# net_monitor.net
KiCad netlist of a schematic drawn in EAGLE
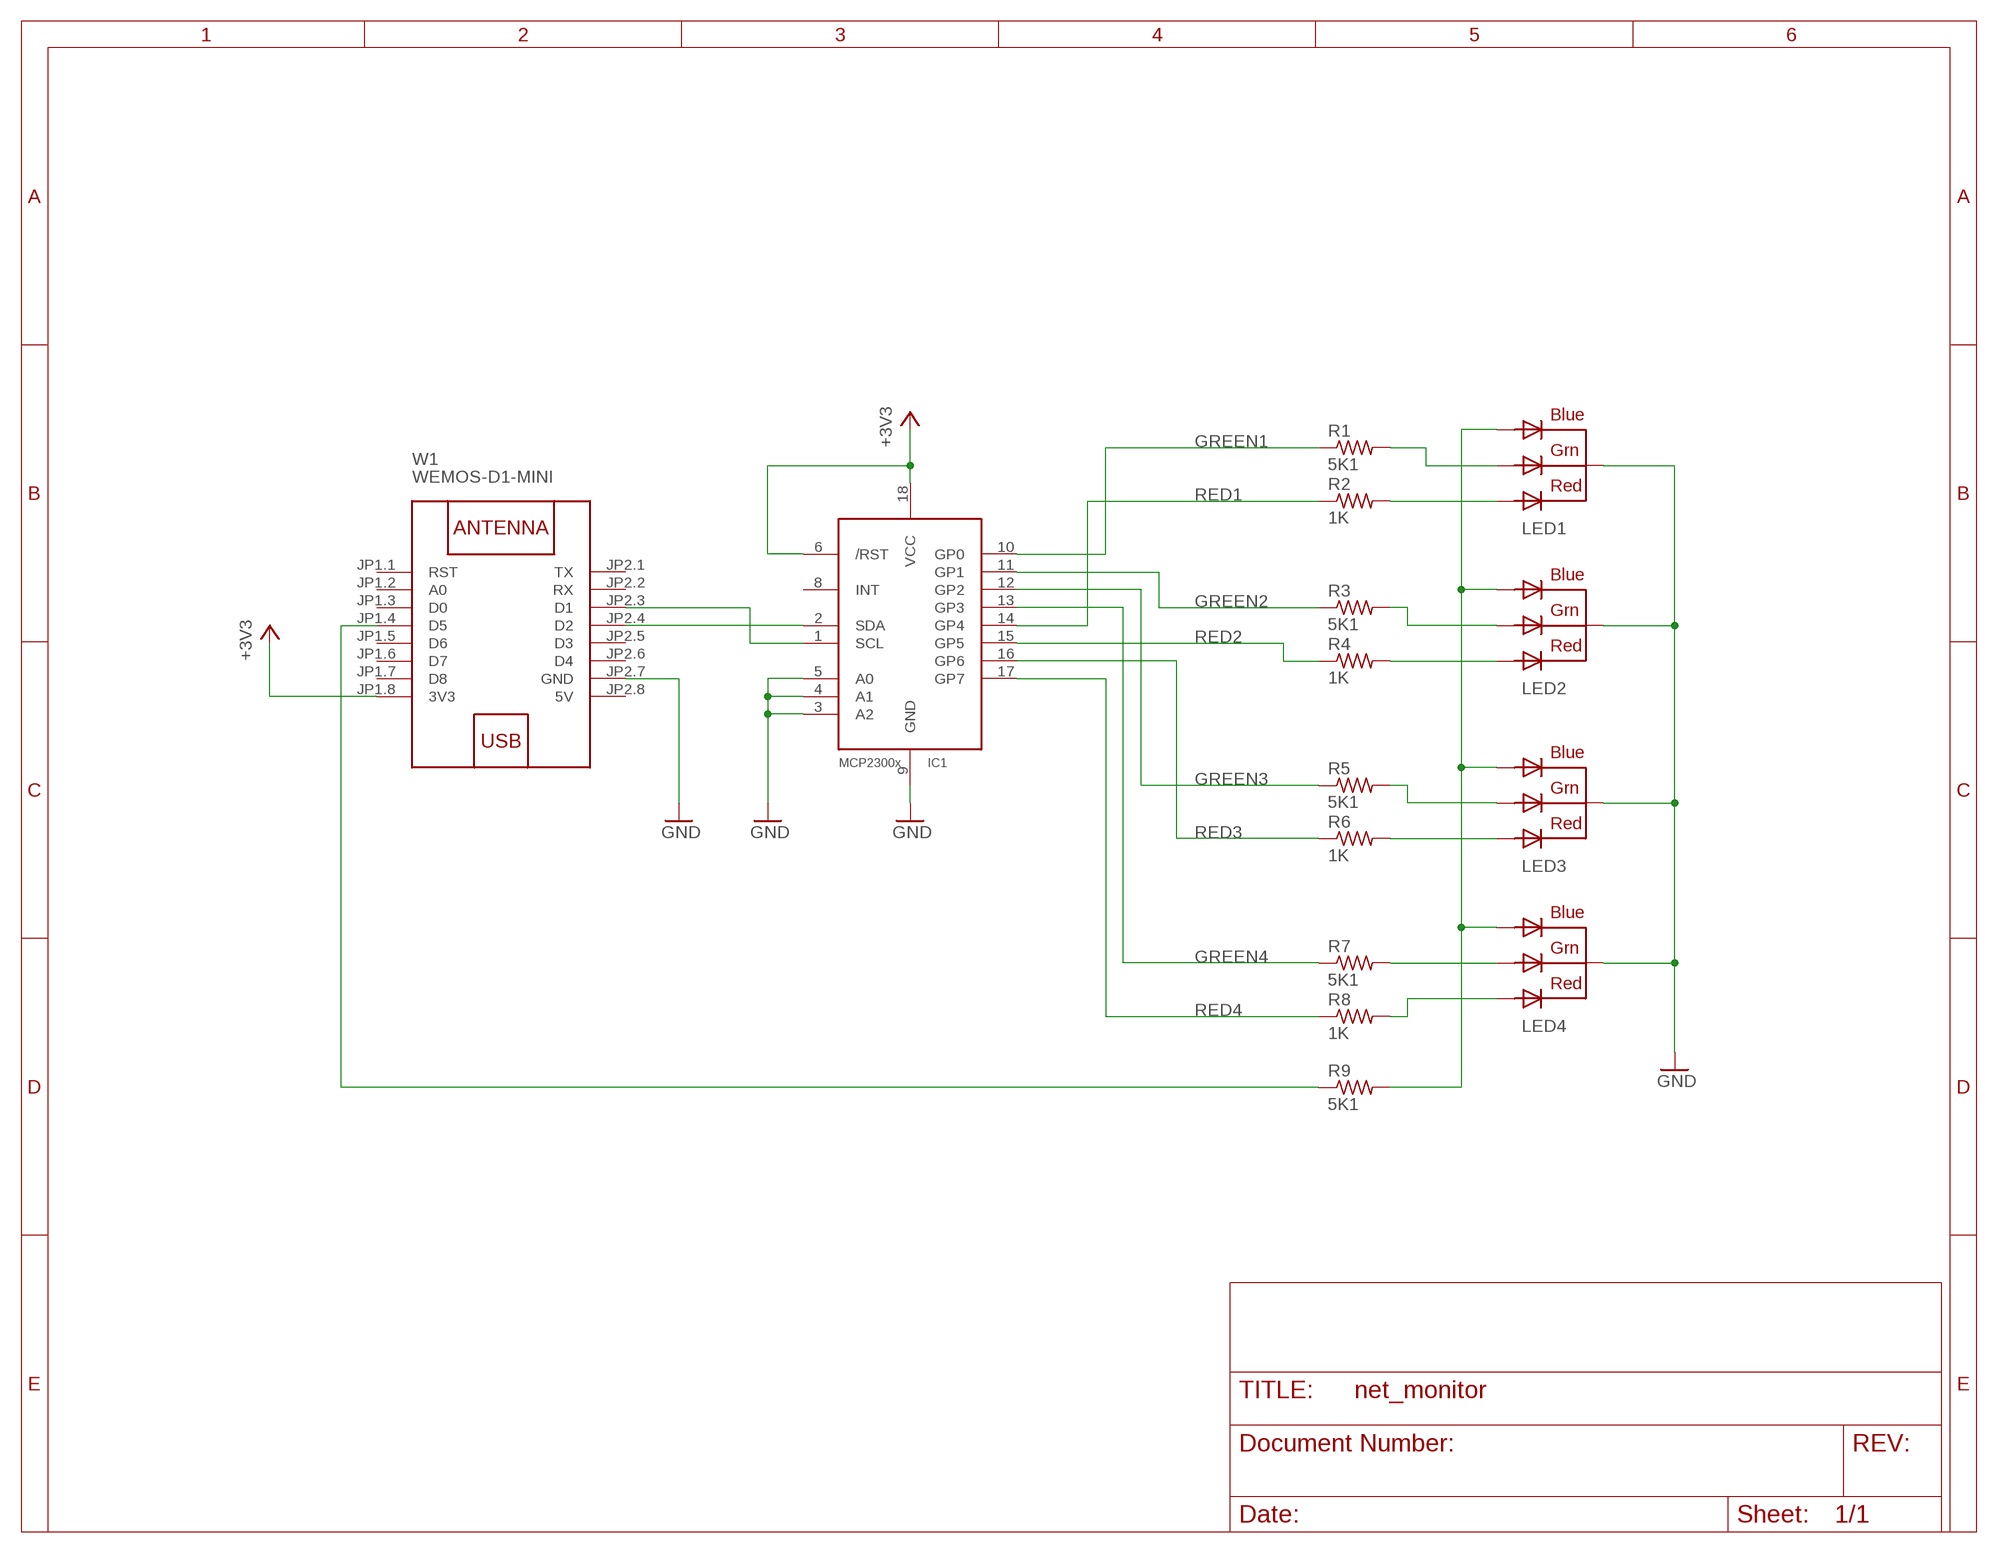
[diagram p0: schematic, sheet 1]

(export (version "E")
  (design (tool "Eeschema 10.0.6"))
  (components
    (comp (ref "IC1")
      (value "MCP23008/P")
      (footprint "eagle-import:DIL18")
      (libsource (lib "eagle-import") (part "MCP23008/P"))
    )
    (comp (ref "LED1")
      (value "RGBLED_CC")
      (footprint "eagle-import:LED5MMRGB")
      (libsource (lib "eagle-import") (part "RGBLED_CC"))
    )
    (comp (ref "LED2")
      (value "RGBLED_CC")
      (footprint "eagle-import:LED5MMRGB")
      (libsource (lib "eagle-import") (part "RGBLED_CC"))
    )
    (comp (ref "LED3")
      (value "RGBLED_CC")
      (footprint "eagle-import:LED5MMRGB")
      (libsource (lib "eagle-import") (part "RGBLED_CC"))
    )
    (comp (ref "LED4")
      (value "RGBLED_CC")
      (footprint "eagle-import:LED5MMRGB")
      (libsource (lib "eagle-import") (part "RGBLED_CC"))
    )
    (comp (ref "R1")
      (value "5K1")
      (footprint "eagle-import:0207_10")
      (fields (field (name "MPN") "CRCW12065K10FKEA"))
      (libsource (lib "eagle-import") (part "R-US_0207/10"))
    )
    (comp (ref "R2")
      (value "1K")
      (footprint "eagle-import:0207_10")
      (libsource (lib "eagle-import") (part "R-US_0207/10"))
    )
    (comp (ref "R3")
      (value "5K1")
      (footprint "eagle-import:0207_10")
      (fields (field (name "MPN") "CRCW12065K10FKEA"))
      (libsource (lib "eagle-import") (part "R-US_0207/10"))
    )
    (comp (ref "R4")
      (value "1K")
      (footprint "eagle-import:0207_10")
      (libsource (lib "eagle-import") (part "R-US_0207/10"))
    )
    (comp (ref "R5")
      (value "5K1")
      (footprint "eagle-import:0207_10")
      (fields (field (name "MPN") "CRCW12065K10FKEA"))
      (libsource (lib "eagle-import") (part "R-US_0207/10"))
    )
    (comp (ref "R6")
      (value "1K")
      (footprint "eagle-import:0207_10")
      (libsource (lib "eagle-import") (part "R-US_0207/10"))
    )
    (comp (ref "R7")
      (value "5K1")
      (footprint "eagle-import:0207_10")
      (fields (field (name "MPN") "CRCW12065K10FKEA"))
      (libsource (lib "eagle-import") (part "R-US_0207/10"))
    )
    (comp (ref "R8")
      (value "1K")
      (footprint "eagle-import:0207_10")
      (libsource (lib "eagle-import") (part "R-US_0207/10"))
    )
    (comp (ref "R9")
      (value "5K1")
      (footprint "eagle-import:0207_10")
      (fields (field (name "MPN") "CRCW12065K10FKEA"))
      (libsource (lib "eagle-import") (part "R-US_0207/10"))
    )
    (comp (ref "W1")
      (value "WEMOS-D1-MINI")
      (footprint "eagle-import:WEMOS-D1-MINI")
      (libsource (lib "eagle-import") (part "WEMOS-D1-MINI"))
    )
  )
  (nets
    (net (code "1") (name "+3V3") (class "Default")
      (node (ref "IC1") (pin "18") (pinfunction "VCC_18") (pintype "power_in"))
      (node (ref "IC1") (pin "6") (pinfunction "/RST_6") (pintype "input"))
      (node (ref "W1") (pin "JP1.8") (pinfunction "3V3_JP1.8") (pintype "power_in"))
    )
    (net (code "2") (name "/5V") (class "Default")
      (node (ref "W1") (pin "JP2.8") (pinfunction "5V_JP2.8") (pintype "power_in"))
    )
    (net (code "3") (name "/GREEN1") (class "Default")
      (node (ref "IC1") (pin "10") (pinfunction "GP0_10") (pintype "bidirectional"))
      (node (ref "R1") (pin "1") (pinfunction "1_1") (pintype "passive"))
    )
    (net (code "4") (name "/GREEN2") (class "Default")
      (node (ref "IC1") (pin "11") (pinfunction "GP1_11") (pintype "bidirectional"))
      (node (ref "R3") (pin "1") (pinfunction "1_1") (pintype "passive"))
    )
    (net (code "5") (name "/GREEN3") (class "Default")
      (node (ref "IC1") (pin "12") (pinfunction "GP2_12") (pintype "bidirectional"))
      (node (ref "R5") (pin "1") (pinfunction "1_1") (pintype "passive"))
    )
    (net (code "6") (name "/GREEN4") (class "Default")
      (node (ref "IC1") (pin "13") (pinfunction "GP3_13") (pintype "bidirectional"))
      (node (ref "R7") (pin "1") (pinfunction "1_1") (pintype "passive"))
    )
    (net (code "7") (name "/RED1") (class "Default")
      (node (ref "IC1") (pin "14") (pinfunction "GP4_14") (pintype "bidirectional"))
      (node (ref "R2") (pin "1") (pinfunction "1_1") (pintype "passive"))
    )
    (net (code "8") (name "/RED2") (class "Default")
      (node (ref "IC1") (pin "15") (pinfunction "GP5_15") (pintype "bidirectional"))
      (node (ref "R4") (pin "1") (pinfunction "1_1") (pintype "passive"))
    )
    (net (code "9") (name "/RED3") (class "Default")
      (node (ref "IC1") (pin "16") (pinfunction "GP6_16") (pintype "bidirectional"))
      (node (ref "R6") (pin "1") (pinfunction "1_1") (pintype "passive"))
    )
    (net (code "10") (name "/RED4") (class "Default")
      (node (ref "IC1") (pin "17") (pinfunction "GP7_17") (pintype "bidirectional"))
      (node (ref "R8") (pin "1") (pinfunction "1_1") (pintype "passive"))
    )
    (net (code "11") (name "GND") (class "Default")
      (node (ref "IC1") (pin "3") (pinfunction "A2_3") (pintype "input"))
      (node (ref "IC1") (pin "4") (pinfunction "A1_4") (pintype "input"))
      (node (ref "IC1") (pin "5") (pinfunction "A0_5") (pintype "input"))
      (node (ref "IC1") (pin "9") (pinfunction "GND_9") (pintype "power_in"))
      (node (ref "LED1") (pin "2") (pinfunction "CATHODE_2") (pintype "bidirectional"))
      (node (ref "LED2") (pin "2") (pinfunction "CATHODE_2") (pintype "bidirectional"))
      (node (ref "LED3") (pin "2") (pinfunction "CATHODE_2") (pintype "bidirectional"))
      (node (ref "LED4") (pin "2") (pinfunction "CATHODE_2") (pintype "bidirectional"))
      (node (ref "W1") (pin "JP2.7") (pinfunction "GND_JP2.7") (pintype "power_in"))
    )
    (net (code "12") (name "Net-(IC1-SCL)") (class "Default")
      (node (ref "IC1") (pin "1") (pinfunction "SCL_1") (pintype "bidirectional"))
      (node (ref "W1") (pin "JP2.3") (pinfunction "D1_JP2.3") (pintype "bidirectional"))
    )
    (net (code "13") (name "Net-(IC1-SDA)") (class "Default")
      (node (ref "IC1") (pin "2") (pinfunction "SDA_2") (pintype "bidirectional"))
      (node (ref "W1") (pin "JP2.4") (pinfunction "D2_JP2.4") (pintype "bidirectional"))
    )
    (net (code "14") (name "Net-(LED1-BLUE)") (class "Default")
      (node (ref "LED1") (pin "4") (pinfunction "BLUE_4") (pintype "bidirectional"))
      (node (ref "LED2") (pin "4") (pinfunction "BLUE_4") (pintype "bidirectional"))
      (node (ref "LED3") (pin "4") (pinfunction "BLUE_4") (pintype "bidirectional"))
      (node (ref "LED4") (pin "4") (pinfunction "BLUE_4") (pintype "bidirectional"))
      (node (ref "R9") (pin "2") (pinfunction "2_2") (pintype "passive"))
    )
    (net (code "15") (name "Net-(LED1-GREEN)") (class "Default")
      (node (ref "LED1") (pin "3") (pinfunction "GREEN_3") (pintype "bidirectional"))
      (node (ref "R1") (pin "2") (pinfunction "2_2") (pintype "passive"))
    )
    (net (code "16") (name "Net-(LED1-RED)") (class "Default")
      (node (ref "LED1") (pin "1") (pinfunction "RED_1") (pintype "bidirectional"))
      (node (ref "R2") (pin "2") (pinfunction "2_2") (pintype "passive"))
    )
    (net (code "17") (name "Net-(LED2-GREEN)") (class "Default")
      (node (ref "LED2") (pin "3") (pinfunction "GREEN_3") (pintype "bidirectional"))
      (node (ref "R3") (pin "2") (pinfunction "2_2") (pintype "passive"))
    )
    (net (code "18") (name "Net-(LED2-RED)") (class "Default")
      (node (ref "LED2") (pin "1") (pinfunction "RED_1") (pintype "bidirectional"))
      (node (ref "R4") (pin "2") (pinfunction "2_2") (pintype "passive"))
    )
    (net (code "19") (name "Net-(LED3-GREEN)") (class "Default")
      (node (ref "LED3") (pin "3") (pinfunction "GREEN_3") (pintype "bidirectional"))
      (node (ref "R5") (pin "2") (pinfunction "2_2") (pintype "passive"))
    )
    (net (code "20") (name "Net-(LED3-RED)") (class "Default")
      (node (ref "LED3") (pin "1") (pinfunction "RED_1") (pintype "bidirectional"))
      (node (ref "R6") (pin "2") (pinfunction "2_2") (pintype "passive"))
    )
    (net (code "21") (name "Net-(LED4-GREEN)") (class "Default")
      (node (ref "LED4") (pin "3") (pinfunction "GREEN_3") (pintype "bidirectional"))
      (node (ref "R7") (pin "2") (pinfunction "2_2") (pintype "passive"))
    )
    (net (code "22") (name "Net-(LED4-RED)") (class "Default")
      (node (ref "LED4") (pin "1") (pinfunction "RED_1") (pintype "bidirectional"))
      (node (ref "R8") (pin "2") (pinfunction "2_2") (pintype "passive"))
    )
    (net (code "23") (name "Net-(W1-D5)") (class "Default")
      (node (ref "R9") (pin "1") (pinfunction "1_1") (pintype "passive"))
      (node (ref "W1") (pin "JP1.4") (pinfunction "D5_JP1.4") (pintype "bidirectional"))
    )
    (net (code "24") (name "unconnected-(IC1-INT-Pad8)") (class "Default")
      (node (ref "IC1") (pin "8") (pinfunction "INT_8") (pintype "output"))
    )
    (net (code "25") (name "unconnected-(W1-A0-PadJP1.2)") (class "Default")
      (node (ref "W1") (pin "JP1.2") (pinfunction "A0_JP1.2") (pintype "bidirectional"))
    )
    (net (code "26") (name "unconnected-(W1-D0-PadJP1.3)") (class "Default")
      (node (ref "W1") (pin "JP1.3") (pinfunction "D0_JP1.3") (pintype "bidirectional"))
    )
    (net (code "27") (name "unconnected-(W1-D3-PadJP2.5)") (class "Default")
      (node (ref "W1") (pin "JP2.5") (pinfunction "D3_JP2.5") (pintype "bidirectional"))
    )
    (net (code "28") (name "unconnected-(W1-D4-PadJP2.6)") (class "Default")
      (node (ref "W1") (pin "JP2.6") (pinfunction "D4_JP2.6") (pintype "bidirectional"))
    )
    (net (code "29") (name "unconnected-(W1-D6-PadJP1.5)") (class "Default")
      (node (ref "W1") (pin "JP1.5") (pinfunction "D6_JP1.5") (pintype "bidirectional"))
    )
    (net (code "30") (name "unconnected-(W1-D7-PadJP1.6)") (class "Default")
      (node (ref "W1") (pin "JP1.6") (pinfunction "D7_JP1.6") (pintype "bidirectional"))
    )
    (net (code "31") (name "unconnected-(W1-D8-PadJP1.7)") (class "Default")
      (node (ref "W1") (pin "JP1.7") (pinfunction "D8_JP1.7") (pintype "bidirectional"))
    )
    (net (code "32") (name "unconnected-(W1-RST-PadJP1.1)") (class "Default")
      (node (ref "W1") (pin "JP1.1") (pinfunction "RST_JP1.1") (pintype "bidirectional"))
    )
    (net (code "33") (name "unconnected-(W1-RX-PadJP2.2)") (class "Default")
      (node (ref "W1") (pin "JP2.2") (pinfunction "RX_JP2.2") (pintype "bidirectional"))
    )
    (net (code "34") (name "unconnected-(W1-TX-PadJP2.1)") (class "Default")
      (node (ref "W1") (pin "JP2.1") (pinfunction "TX_JP2.1") (pintype "bidirectional"))
    )
  )
)
